# TailLightPrototypeRev3.net
KiCad netlist of a schematic drawn in Altium Designer
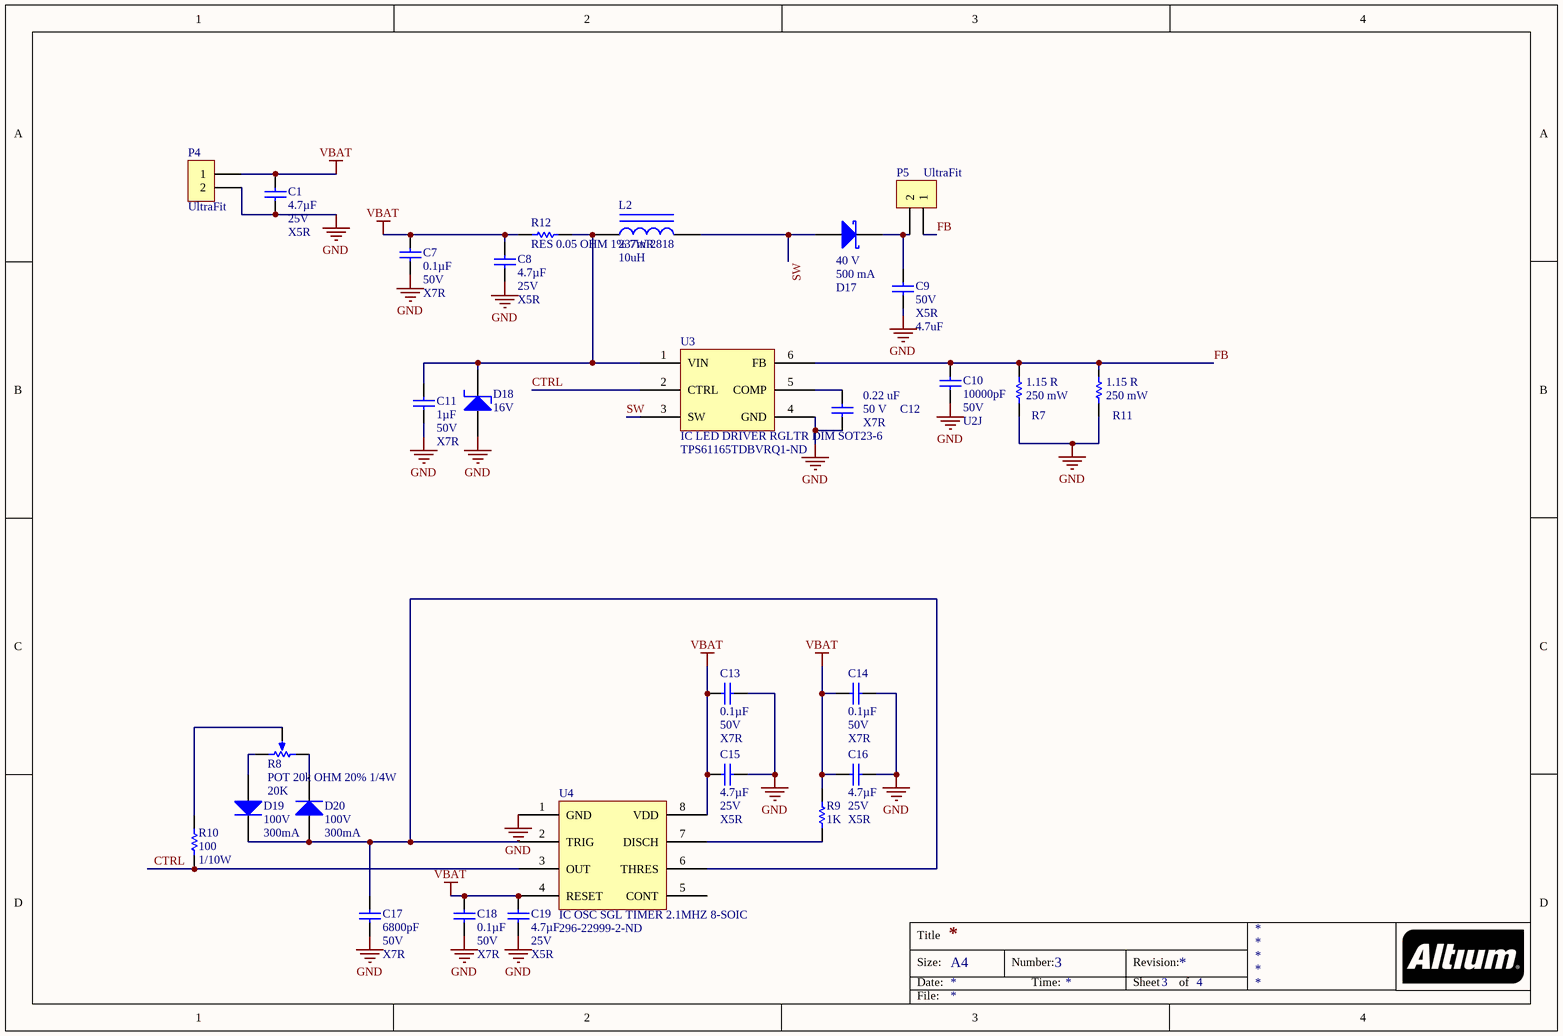
[diagram p0: TailLightPrototypeRev3.SchDoc]

(export (version "E")
  (design (tool "Eeschema 10.0.6"))
  (components
    (comp (ref "C1")
      (value "CAP CER 4.7UF 25V 10% X5R 0603")
      (footprint "CAP, 0603")
      (description "4.7µF ±10% 25V Ceramic Capacitor X5R 0603 (1608 Metric)")
      (fields
        (field (name "TOLERANCE") "±10%")
        (field (name "CAPACITANCE") "4.7µF")
        (field (name "VOLTAGE") "25V")
        (field (name "TEMPERATURE COEFFICIENT") "X5R")
      )
      (libsource (lib "Schematic Diagrams") (part "CAP CER 4.7UF 25V 10% X5R 0603"))
    )
    (comp (ref "C7")
      (value "CAP CER 0.1UF 50V 10% X7R 0603")
      (footprint "CAP, 0603")
      (description "0.10µF ±10% 50V Ceramic Capacitor X7R 0603 (1608 Metric)")
      (fields
        (field (name "TOLERANCE") "±10%")
        (field (name "CAPACITANCE") "0.1µF")
        (field (name "VOLTAGE") "50V")
        (field (name "TEMPERATURE COEFFICIENT") "X7R")
      )
      (libsource (lib "Schematic Diagrams") (part "CAP CER 0.1UF 50V 10% X7R 0603"))
    )
    (comp (ref "C8")
      (value "CAP CER 4.7UF 25V 10% X5R 0603")
      (footprint "CAP, 0603")
      (description "4.7µF ±10% 25V Ceramic Capacitor X5R 0603 (1608 Metric)")
      (fields
        (field (name "TOLERANCE") "±10%")
        (field (name "CAPACITANCE") "4.7µF")
        (field (name "VOLTAGE") "25V")
        (field (name "TEMPERATURE COEFFICIENT") "X5R")
      )
      (libsource (lib "Schematic Diagrams") (part "CAP CER 4.7UF 25V 10% X5R 0603"))
    )
    (comp (ref "C9")
      (value "4.7uF")
      (footprint "CAP, 0805")
      (description "4.7µF ±20% 50V Ceramic Capacitor X5R 0805 (2012 Metric)")
      (fields
        (field (name "TOLERANCE") "±20%")
        (field (name "VOLTAGE - RATED") "50V")
        (field (name "TEMPERATURE COEFFICIENT") "X5R")
        (field (name "Comment") "CAP CER 4.7UF 50V 10% X5R 0805")
      )
      (libsource (lib "Schematic Diagrams") (part "CAP CER 4.7UF 50V 10% X5R 0805"))
    )
    (comp (ref "C10")
      (value "CAP CER 10nF 50V 5% X7R 0603")
      (footprint "CAP, 0603")
      (description "10000pF ±5% 50V Ceramic Capacitor U2J 0603 (1608 Metric)")
      (fields
        (field (name "TOLERANCE") "±5%")
        (field (name "CAPACITANCE") "10000pF")
        (field (name "VOLTAGE") "50V")
        (field (name "TEMPERATURE COEFFICIENT") "U2J")
      )
      (libsource (lib "Schematic Diagrams") (part "CAP CER 10nF 50V 5% X7R 0603"))
    )
    (comp (ref "C11")
      (value "CAP CER 1UF 50V 10% X7R 0603")
      (footprint "CAP, 0603")
      (description "1µF ±10% 50V Ceramic Capacitor X7R 0603 (1608 Metric)")
      (fields
        (field (name "TOLERANCE") "±10%")
        (field (name "CAPACITANCE") "1µF")
        (field (name "VOLTAGE") "50V")
        (field (name "TEMPERATURE COEFFICIENT") "X7R")
      )
      (libsource (lib "Schematic Diagrams") (part "CAP CER 1UF 50V 10% X7R 0603"))
    )
    (comp (ref "C12")
      (value "CAP CER 0.22UF 50V X7R 0805")
      (footprint "CAP, 0805")
      (fields
        (field (name "MANUFACTURER") "Samsung")
        (field (name "MANUFACTURER PART NUMBER") "CL21B224KBFNNNE")
        (field (name "TOLERANCE") "10%")
      )
      (libsource (lib "Schematic Diagrams") (part "CAP CER 0.22UF 50V X7R 0805"))
    )
    (comp (ref "C13")
      (value "CAP CER 0.1UF 50V 10% X7R 0603")
      (footprint "CAP, 0603")
      (description "0.10µF ±10% 50V Ceramic Capacitor X7R 0603 (1608 Metric)")
      (fields
        (field (name "TOLERANCE") "±10%")
        (field (name "CAPACITANCE") "0.1µF")
        (field (name "VOLTAGE") "50V")
        (field (name "TEMPERATURE COEFFICIENT") "X7R")
      )
      (libsource (lib "Schematic Diagrams") (part "CAP CER 0.1UF 50V 10% X7R 0603"))
    )
    (comp (ref "C14")
      (value "CAP CER 0.1UF 50V 10% X7R 0603")
      (footprint "CAP, 0603")
      (description "0.10µF ±10% 50V Ceramic Capacitor X7R 0603 (1608 Metric)")
      (fields
        (field (name "TOLERANCE") "±10%")
        (field (name "CAPACITANCE") "0.1µF")
        (field (name "VOLTAGE") "50V")
        (field (name "TEMPERATURE COEFFICIENT") "X7R")
      )
      (libsource (lib "Schematic Diagrams") (part "CAP CER 0.1UF 50V 10% X7R 0603"))
    )
    (comp (ref "C15")
      (value "CAP CER 4.7UF 25V 10% X5R 0603")
      (footprint "CAP, 0603")
      (description "4.7µF ±10% 25V Ceramic Capacitor X5R 0603 (1608 Metric)")
      (fields
        (field (name "TOLERANCE") "±10%")
        (field (name "CAPACITANCE") "4.7µF")
        (field (name "VOLTAGE") "25V")
        (field (name "TEMPERATURE COEFFICIENT") "X5R")
      )
      (libsource (lib "Schematic Diagrams") (part "CAP CER 4.7UF 25V 10% X5R 0603"))
    )
    (comp (ref "C16")
      (value "CAP CER 4.7UF 25V 10% X5R 0603")
      (footprint "CAP, 0603")
      (description "4.7µF ±10% 25V Ceramic Capacitor X5R 0603 (1608 Metric)")
      (fields
        (field (name "TOLERANCE") "±10%")
        (field (name "CAPACITANCE") "4.7µF")
        (field (name "VOLTAGE") "25V")
        (field (name "TEMPERATURE COEFFICIENT") "X5R")
      )
      (libsource (lib "Schematic Diagrams") (part "CAP CER 4.7UF 25V 10% X5R 0603"))
    )
    (comp (ref "C17")
      (value "CAP CER 6800pF 50V 10% X7R 0603")
      (footprint "CAP, 0603")
      (description "6800pF ±10% 50V Ceramic Capacitor X7R 0603 (1608 Metric)")
      (fields
        (field (name "TOLERANCE") "±10%")
        (field (name "CAPACITANCE") "6800pF")
        (field (name "VOLTAGE") "50V")
        (field (name "TEMPERATURE COEFFICIENT") "X7R")
      )
      (libsource (lib "Schematic Diagrams") (part "CAP CER 6800pF 50V 10% X7R 0603"))
    )
    (comp (ref "C18")
      (value "CAP CER 0.1UF 50V 10% X7R 0603")
      (footprint "CAP, 0603")
      (description "0.10µF ±10% 50V Ceramic Capacitor X7R 0603 (1608 Metric)")
      (fields
        (field (name "TOLERANCE") "±10%")
        (field (name "CAPACITANCE") "0.1µF")
        (field (name "VOLTAGE") "50V")
        (field (name "TEMPERATURE COEFFICIENT") "X7R")
      )
      (libsource (lib "Schematic Diagrams") (part "CAP CER 0.1UF 50V 10% X7R 0603"))
    )
    (comp (ref "C19")
      (value "CAP CER 4.7UF 25V 10% X5R 0603")
      (footprint "CAP, 0603")
      (description "4.7µF ±10% 25V Ceramic Capacitor X5R 0603 (1608 Metric)")
      (fields
        (field (name "TOLERANCE") "±10%")
        (field (name "CAPACITANCE") "4.7µF")
        (field (name "VOLTAGE") "25V")
        (field (name "TEMPERATURE COEFFICIENT") "X5R")
      )
      (libsource (lib "Schematic Diagrams") (part "CAP CER 4.7UF 25V 10% X5R 0603"))
    )
    (comp (ref "D17")
      (value "DIODE SCHOTTKY 40V 500MA SOD123")
      (footprint "SOD123")
      (description "Diode Schottky 40V 500mA Surface Mount SOD-123")
      (fields
        (field (name "MANUFACTURER") "ON Semiconductor / Fairchild")
        (field (name "MANUFACTURER PART NUMBER") "MBR0540")
      )
      (libsource (lib "Schematic Diagrams") (part "DIODE SCHOTTKY 40V 500MA SOD123"))
    )
    (comp (ref "D18")
      (value "DIODE ZENER 16V 5W DO-214AA (SMB)")
      (footprint "DO-214AA Diode")
      (description "Zener Diode 16V 5W ±5% Surface Mount DO-214AA (SMB)")
      (fields
        (field (name "MANUFACTURE PART NUMBER") "SMBJ5353B-TP")
        (field (name "VOLTAGE - ZENER (NOM)") "16V")
      )
      (libsource (lib "Schematic Diagrams") (part "DIODE ZENER 16V 5W DO-214AA (SMB)"))
    )
    (comp (ref "D19")
      (value "DIODE GEN PURP 100V 300MA SOD123")
      (footprint "DIODE GEN PURP 100V 300MA SOD123")
      (description "Diode Standard 100V 300mA (DC) Surface Mount SOD-123")
      (fields
        (field (name "MANUFACTURER") "Diodes Zetex")
        (field (name "MANUFACTURER PART NUMBER") "1N4148WQ-7-F")
        (field (name "MAX REPETITIVE REVERSE VOLTAGE (VRRM)") "100V")
        (field (name "FORWARD CURRENT") "300mA")
      )
      (libsource (lib "Schematic Diagrams") (part "DIODE GEN PURP 100V 300MA SOD123"))
    )
    (comp (ref "D20")
      (value "DIODE GEN PURP 100V 300MA SOD123")
      (footprint "DIODE GEN PURP 100V 300MA SOD123")
      (description "Diode Standard 100V 300mA (DC) Surface Mount SOD-123")
      (fields
        (field (name "MANUFACTURER") "Diodes Zetex")
        (field (name "MANUFACTURER PART NUMBER") "1N4148WQ-7-F")
        (field (name "MAX REPETITIVE REVERSE VOLTAGE (VRRM)") "100V")
        (field (name "FORWARD CURRENT") "300mA")
      )
      (libsource (lib "Schematic Diagrams") (part "DIODE GEN PURP 100V 300MA SOD123"))
    )
    (comp (ref "L2")
      (value "FIXED IND 10UH 1.13A 237 MOHM")
      (footprint "INDP5050X20N")
      (description "10µH Shielded Wirewound Inductor 1.13A 237mOhm Max Nonstandard")
      (fields
        (field (name "MANUFACTURER") "TDK")
        (field (name "MANUFACTURER PART NUMBER") "VLCF5020T-100M1R1-1")
        (field (name "DC RESISTANCE (DCR)") "237mR")
        (field (name "INDUCTANCE") "10uH")
      )
      (libsource (lib "Schematic Diagrams") (part "FIXED IND 10UH 1.13A 237 MOHM"))
    )
    (comp (ref "P4")
      (value "CONN 2POS ULTRA-FIT 0.138\"")
      (footprint "CONN, 2POS ULTRA-FIT")
      (description "Connector Header Through Hole 2 position 0.138\" (3.50mm)")
      (fields
        (field (name "MANUFACTURER") "Molex")
        (field (name "MANUFACTURER PART NUMBER") "1722871102")
        (field (name "SERIES") "UltraFit")
      )
      (libsource (lib "Schematic Diagrams") (part "CONN 2POS ULTRA-FIT 0.138{dblquote}"))
    )
    (comp (ref "P5")
      (value "CONN 2POS ULTRA-FIT 0.138\"")
      (footprint "CONN, 2POS ULTRA-FIT")
      (description "2 Positions Header, Shrouded Connector 0.138\" (3.50mm) Through Hole Gold")
      (fields (field (name "VOLTAGE") "400V") (field (name "SERIES") "UltraFit"))
      (libsource (lib "") (part "CONN 2POS ULTRA-FIT 0.138{dblquote}_1"))
    )
    (comp (ref "R7")
      (value "RES SMD 1.15 OHM 1% 1/4W 1206")
      (footprint "RES 1206")
      (fields
        (field (name "MANUFACTURER") "Yageo")
        (field (name "MANUFACTURER PART NUMBER") "RC1206FR-071R15L")
        (field (name "TOLERANCE") "1%")
      )
      (libsource (lib "Schematic Diagrams") (part "RES SMD 1.15 OHM 1% 1/4W 1206"))
    )
    (comp (ref "R8")
      (value "POT 20k OHM 20% 1/4W")
      (footprint "20K POT")
      (description "20k Ohm 0.25W, 1/4W Gull Wing Surface Mount Trimmer Potentiometer")
      (fields
        (field (name "POWER") "1/4W")
        (field (name "MANUFACTURE PART NUMBER") "23BR20KLFTR")
        (field (name "ALTIUM_VALUE") "20K")
      )
      (libsource (lib "Schematic Diagrams") (part "POT 20k OHM 20% 1/4W"))
    )
    (comp (ref "R9")
      (value "1K")
      (footprint "RES, 0603")
      (description "1k Ohm ±5% 0.1W, 1/10W Chip Resistor 0603 (1608 Metric)")
      (fields
        (field (name "MANUFACTURER") "Yageo")
        (field (name "MANUFACTURER PART NUMBER") "RC0603JR-071KL")
      )
      (libsource (lib "Schematic Diagrams") (part "RES 1K OHM 5% 1/10W 0603"))
    )
    (comp (ref "R10")
      (value "RES 100 OHM 1% 1/10W 0603")
      (footprint "RES, 0603")
      (description "100 Ohm ±1% 0.1W, 1/10W Chip Resistor 0603 (1608 Metric) Moisture Resistant Thick Film")
      (fields
        (field (name "TOLERANCE") "±1%")
        (field (name "RESISTANCE") "100")
        (field (name "POWER") "1/10W")
      )
      (libsource (lib "Schematic Diagrams") (part "RES 100 OHM 1% 1/10W 0603"))
    )
    (comp (ref "R11")
      (value "RES SMD 1.15 OHM 1% 1/4W 1206")
      (footprint "RES 1206")
      (fields
        (field (name "MANUFACTURER") "Yageo")
        (field (name "MANUFACTURER PART NUMBER") "RC1206FR-071R15L")
        (field (name "TOLERANCE") "1%")
      )
      (libsource (lib "Schematic Diagrams") (part "RES SMD 1.15 OHM 1% 1/4W 1206"))
    )
    (comp (ref "R12")
      (value "RES 0.05 OHM 1% 7W 2818")
      (footprint "RES 2818")
      (fields (field (name "TOLERANCE") "1%"))
      (libsource (lib "Schematic Diagrams") (part "RES 0.05 OHM 1% 7W 2818"))
    )
    (comp (ref "U3")
      (value "IC LED DRIVER RGLTR DIM SOT23-6")
      (footprint "SOT23-6_N")
      (description "LED Driver IC 1 Output DC DC Regulator Step-Up (Boost) PWM Dimming 1.2A (Switch) SOT-23-6")
      (fields
        (field (name "MANUFACTURER") "Texas Instruments")
        (field (name "MANUFACTURER PART NUMBER") "TPS61165TDBVRQ1")
        (field (name "SUPPLIER PART NUMBER 1") "TPS61165TDBVRQ1-ND")
      )
      (libsource (lib "Schematic Diagrams") (part "IC LED DRIVER RGLTR DIM SOT23-6"))
    )
    (comp (ref "U4")
      (value "IC OSC SGL TIMER 2.1MHZ 8-SOIC")
      (footprint "SOIC8")
      (description "555 Type, Timer/Oscillator (Single) IC 2.1MHz 8-SOIC")
      (fields
        (field (name "MANUFACTURER") "Texas Instruments")
        (field (name "MANUFACTURER PART NUMBER") "TLC555QDRQ1")
        (field (name "SUPPLIER PART NUMBER 1") "296-22999-2-ND")
      )
      (libsource (lib "Schematic Diagrams") (part "IC OSC SGL TIMER 2.1MHZ 8-SOIC"))
    )
  )
  (nets
    (net (code "1") (name "/CTRL") (class "Default")
      (node (ref "R10") (pin "2") (pinfunction "2_2") (pintype "passive"))
      (node (ref "U3") (pin "2") (pinfunction "CTRL_2") (pintype "passive"))
      (node (ref "U4") (pin "3") (pinfunction "OUT_3") (pintype "passive"))
    )
    (net (code "2") (name "/FB") (class "Default")
      (node (ref "C10") (pin "1") (pinfunction "1_1") (pintype "passive"))
      (node (ref "P5") (pin "1") (pinfunction "1_1") (pintype "passive"))
      (node (ref "R11") (pin "1") (pinfunction "1_1") (pintype "passive"))
      (node (ref "R7") (pin "1") (pinfunction "1_1") (pintype "passive"))
      (node (ref "U3") (pin "6") (pinfunction "FB_6") (pintype "passive"))
    )
    (net (code "3") (name "/SW") (class "Default")
      (node (ref "D17") (pin "1") (pinfunction "A_1") (pintype "passive"))
      (node (ref "L2") (pin "2") (pinfunction "2_2") (pintype "passive"))
      (node (ref "U3") (pin "3") (pinfunction "SW_3") (pintype "passive"))
    )
    (net (code "4") (name "GND") (class "Default")
      (node (ref "C1") (pin "2") (pinfunction "2_2") (pintype "passive"))
      (node (ref "C10") (pin "2") (pinfunction "2_2") (pintype "passive"))
      (node (ref "C11") (pin "2") (pinfunction "2_2") (pintype "passive"))
      (node (ref "C12") (pin "2") (pinfunction "2_2") (pintype "passive"))
      (node (ref "C13") (pin "1") (pinfunction "1_1") (pintype "passive"))
      (node (ref "C14") (pin "1") (pinfunction "1_1") (pintype "passive"))
      (node (ref "C15") (pin "1") (pinfunction "1_1") (pintype "passive"))
      (node (ref "C16") (pin "1") (pinfunction "1_1") (pintype "passive"))
      (node (ref "C17") (pin "2") (pinfunction "2_2") (pintype "passive"))
      (node (ref "C18") (pin "2") (pinfunction "2_2") (pintype "passive"))
      (node (ref "C19") (pin "2") (pinfunction "2_2") (pintype "passive"))
      (node (ref "C7") (pin "2") (pinfunction "2_2") (pintype "passive"))
      (node (ref "C8") (pin "2") (pinfunction "2_2") (pintype "passive"))
      (node (ref "C9") (pin "2") (pinfunction "2_2") (pintype "passive"))
      (node (ref "D18") (pin "1") (pinfunction "A_1") (pintype "passive"))
      (node (ref "P4") (pin "2") (pinfunction "2_2") (pintype "passive"))
      (node (ref "R11") (pin "2") (pinfunction "2_2") (pintype "passive"))
      (node (ref "R7") (pin "2") (pinfunction "2_2") (pintype "passive"))
      (node (ref "U3") (pin "4") (pinfunction "GND_4") (pintype "passive"))
      (node (ref "U4") (pin "1") (pinfunction "GND_1") (pintype "passive"))
    )
    (net (code "5") (name "Net-(D17-K)") (class "Default")
      (node (ref "C9") (pin "1") (pinfunction "1_1") (pintype "passive"))
      (node (ref "D17") (pin "2") (pinfunction "K_2") (pintype "passive"))
      (node (ref "P5") (pin "2") (pinfunction "2_2") (pintype "passive"))
    )
    (net (code "6") (name "Net-(D18-K)") (class "Default")
      (node (ref "C11") (pin "1") (pinfunction "1_1") (pintype "passive"))
      (node (ref "D18") (pin "2") (pinfunction "K_2") (pintype "passive"))
      (node (ref "L2") (pin "1") (pinfunction "1_1") (pintype "passive"))
      (node (ref "R12") (pin "2") (pinfunction "2_2") (pintype "passive"))
      (node (ref "U3") (pin "1") (pinfunction "VIN_1") (pintype "passive"))
    )
    (net (code "7") (name "Net-(D19-A)") (class "Default")
      (node (ref "D19") (pin "1") (pinfunction "A_1") (pintype "passive"))
      (node (ref "R8") (pin "3") (pinfunction "BOT_3") (pintype "passive"))
    )
    (net (code "8") (name "Net-(D19-K)") (class "Default")
      (node (ref "C17") (pin "1") (pinfunction "1_1") (pintype "passive"))
      (node (ref "D19") (pin "2") (pinfunction "K_2") (pintype "passive"))
      (node (ref "D20") (pin "1") (pinfunction "A_1") (pintype "passive"))
      (node (ref "U4") (pin "2") (pinfunction "TRIG_2") (pintype "passive"))
      (node (ref "U4") (pin "6") (pinfunction "THRES_6") (pintype "passive"))
    )
    (net (code "9") (name "Net-(D20-K)") (class "Default")
      (node (ref "D20") (pin "2") (pinfunction "K_2") (pintype "passive"))
      (node (ref "R8") (pin "1") (pinfunction "TOP_1") (pintype "passive"))
    )
    (net (code "10") (name "Net-(R8-TAP)") (class "Default")
      (node (ref "R10") (pin "1") (pinfunction "1_1") (pintype "passive"))
      (node (ref "R8") (pin "2") (pinfunction "TAP_2") (pintype "passive"))
    )
    (net (code "11") (name "Net-(U3-COMP)") (class "Default")
      (node (ref "C12") (pin "1") (pinfunction "1_1") (pintype "passive"))
      (node (ref "U3") (pin "5") (pinfunction "COMP_5") (pintype "passive"))
    )
    (net (code "12") (name "Net-(U4-DISCH)") (class "Default")
      (node (ref "R9") (pin "2") (pinfunction "2_2") (pintype "passive"))
      (node (ref "U4") (pin "7") (pinfunction "DISCH_7") (pintype "passive"))
    )
    (net (code "13") (name "VBAT") (class "Default")
      (node (ref "C1") (pin "1") (pinfunction "1_1") (pintype "passive"))
      (node (ref "C13") (pin "2") (pinfunction "2_2") (pintype "passive"))
      (node (ref "C14") (pin "2") (pinfunction "2_2") (pintype "passive"))
      (node (ref "C15") (pin "2") (pinfunction "2_2") (pintype "passive"))
      (node (ref "C16") (pin "2") (pinfunction "2_2") (pintype "passive"))
      (node (ref "C18") (pin "1") (pinfunction "1_1") (pintype "passive"))
      (node (ref "C19") (pin "1") (pinfunction "1_1") (pintype "passive"))
      (node (ref "C7") (pin "1") (pinfunction "1_1") (pintype "passive"))
      (node (ref "C8") (pin "1") (pinfunction "1_1") (pintype "passive"))
      (node (ref "P4") (pin "1") (pinfunction "1_1") (pintype "passive"))
      (node (ref "R12") (pin "1") (pinfunction "1_1") (pintype "passive"))
      (node (ref "R9") (pin "1") (pinfunction "1_1") (pintype "passive"))
      (node (ref "U4") (pin "4") (pinfunction "RESET_4") (pintype "passive"))
      (node (ref "U4") (pin "8") (pinfunction "VDD_8") (pintype "passive"))
    )
    (net (code "14") (name "unconnected-(U4-CONT-Pad5)") (class "Default")
      (node (ref "U4") (pin "5") (pinfunction "CONT_5") (pintype "passive"))
    )
  )
)
